# PDOC_Filtering.net
KiCad netlist of a schematic drawn in Altium Designer
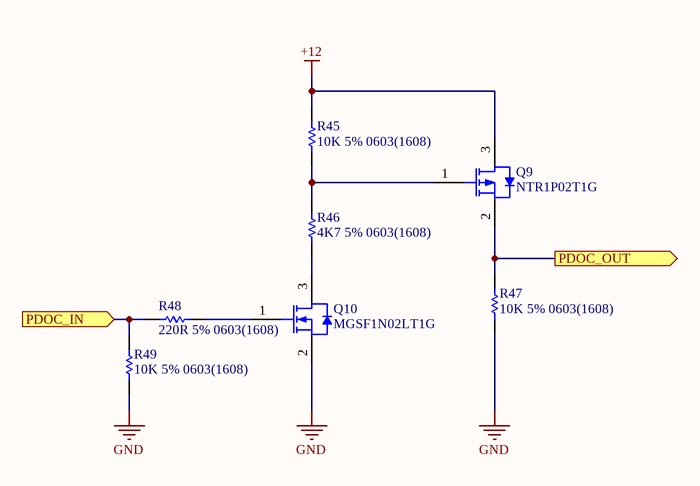
[diagram p0: PDOC_Filtering.SchDoc]

(export (version "E")
  (design (tool "Eeschema 10.0.6"))
  (components
    (comp (ref "Q9")
      (value "NTR1P02T1G")
      (footprint "ONSC-SOT-23-3-318-08_V")
      (description "Power MOSFET, -20 V, -1 A, P-Channel, 3-Pin SOT-23, Pb-Free, Tape and Reel")
      (fields (field (name "MANUFACTURER") "On Semiconductor"))
      (libsource (lib "Altium Content Vault") (part "ONSC-PMOS-G1S2D3-3_D"))
    )
    (comp (ref "Q10")
      (value "MGSF1N02LT1G")
      (footprint "ONSC-SOT-23-3-318-08_V")
      (description "Power MOSFET, 750 mA, 20 V, N-Channel, 3-Pin SOT-23, Pb-Free, Tape and Reel")
      (fields (field (name "MANUFACTURER") "On Semiconductor"))
      (libsource (lib "Altium Content Vault") (part "ONSC-NMOS-G1S2D3-3"))
    )
    (comp (ref "R45")
      (value "10K 5% 0603(1608)")
      (footprint "RESC0603(1608)_N")
      (description "10K 0.1W 5% 0603 (1608 Metric)  SMD")
      (fields (field (name "TOLERANCE") "5 %") (field (name "POWER") "0.1 W"))
      (libsource (lib "Altium Content Vault") (part "RES"))
    )
    (comp (ref "R46")
      (value "4K7 5% 0603(1608)")
      (footprint "RESC0603(1608)_N")
      (description "4K7 0.1W 5% 0603 (1608 Metric)  SMD")
      (fields (field (name "TOLERANCE") "5 %") (field (name "POWER") "0.1 W"))
      (libsource (lib "Altium Content Vault") (part "RES"))
    )
    (comp (ref "R47")
      (value "10K 5% 0603(1608)")
      (footprint "RESC0603(1608)_N")
      (description "10K 0.1W 5% 0603 (1608 Metric)  SMD")
      (fields (field (name "TOLERANCE") "5 %") (field (name "POWER") "0.1 W"))
      (libsource (lib "Altium Content Vault") (part "RES"))
    )
    (comp (ref "R48")
      (value "220R 5% 0603(1608)")
      (footprint "RESC0603(1608)_M")
      (description "220R 0.1W 5% 0603 (1608 Metric)  SMD")
      (fields (field (name "POWER") "0.1 W") (field (name "TOLERANCE") "5 %"))
      (libsource (lib "Altium Content Vault") (part "RES"))
    )
    (comp (ref "R49")
      (value "10K 5% 0603(1608)")
      (footprint "RESC0603(1608)_N")
      (description "10K 0.1W 5% 0603 (1608 Metric)  SMD")
      (fields (field (name "TOLERANCE") "5 %") (field (name "POWER") "0.1 W"))
      (libsource (lib "Altium Content Vault") (part "RES"))
    )
  )
  (nets
    (net (code "1") (name "+12") (class "Default")
      (node (ref "Q9") (pin "3") (pinfunction "D_3") (pintype "passive"))
      (node (ref "R45") (pin "2") (pinfunction "2_2") (pintype "passive"))
    )
    (net (code "2") (name "/PDOC_IN") (class "Default")
      (node (ref "R48") (pin "1") (pinfunction "1_1") (pintype "passive"))
      (node (ref "R49") (pin "2") (pinfunction "2_2") (pintype "passive"))
    )
    (net (code "3") (name "/PDOC_OUT") (class "Default")
      (node (ref "Q9") (pin "2") (pinfunction "S_2") (pintype "passive"))
      (node (ref "R47") (pin "2") (pinfunction "2_2") (pintype "passive"))
    )
    (net (code "4") (name "GND") (class "Default")
      (node (ref "Q10") (pin "2") (pinfunction "S_2") (pintype "passive"))
      (node (ref "R47") (pin "1") (pinfunction "1_1") (pintype "passive"))
      (node (ref "R49") (pin "1") (pinfunction "1_1") (pintype "passive"))
    )
    (net (code "5") (name "Net-(Q9-G)") (class "Default")
      (node (ref "Q9") (pin "1") (pinfunction "G_1") (pintype "passive"))
      (node (ref "R45") (pin "1") (pinfunction "1_1") (pintype "passive"))
      (node (ref "R46") (pin "2") (pinfunction "2_2") (pintype "passive"))
    )
    (net (code "6") (name "Net-(Q10-D)") (class "Default")
      (node (ref "Q10") (pin "3") (pinfunction "D_3") (pintype "passive"))
      (node (ref "R46") (pin "1") (pinfunction "1_1") (pintype "passive"))
    )
    (net (code "7") (name "Net-(Q10-G)") (class "Default")
      (node (ref "Q10") (pin "1") (pinfunction "G_1") (pintype "passive"))
      (node (ref "R48") (pin "2") (pinfunction "2_2") (pintype "passive"))
    )
  )
)
